# BaseShieldBrainDuino3Nov2016.net
KiCad netlist of a schematic drawn in EAGLE
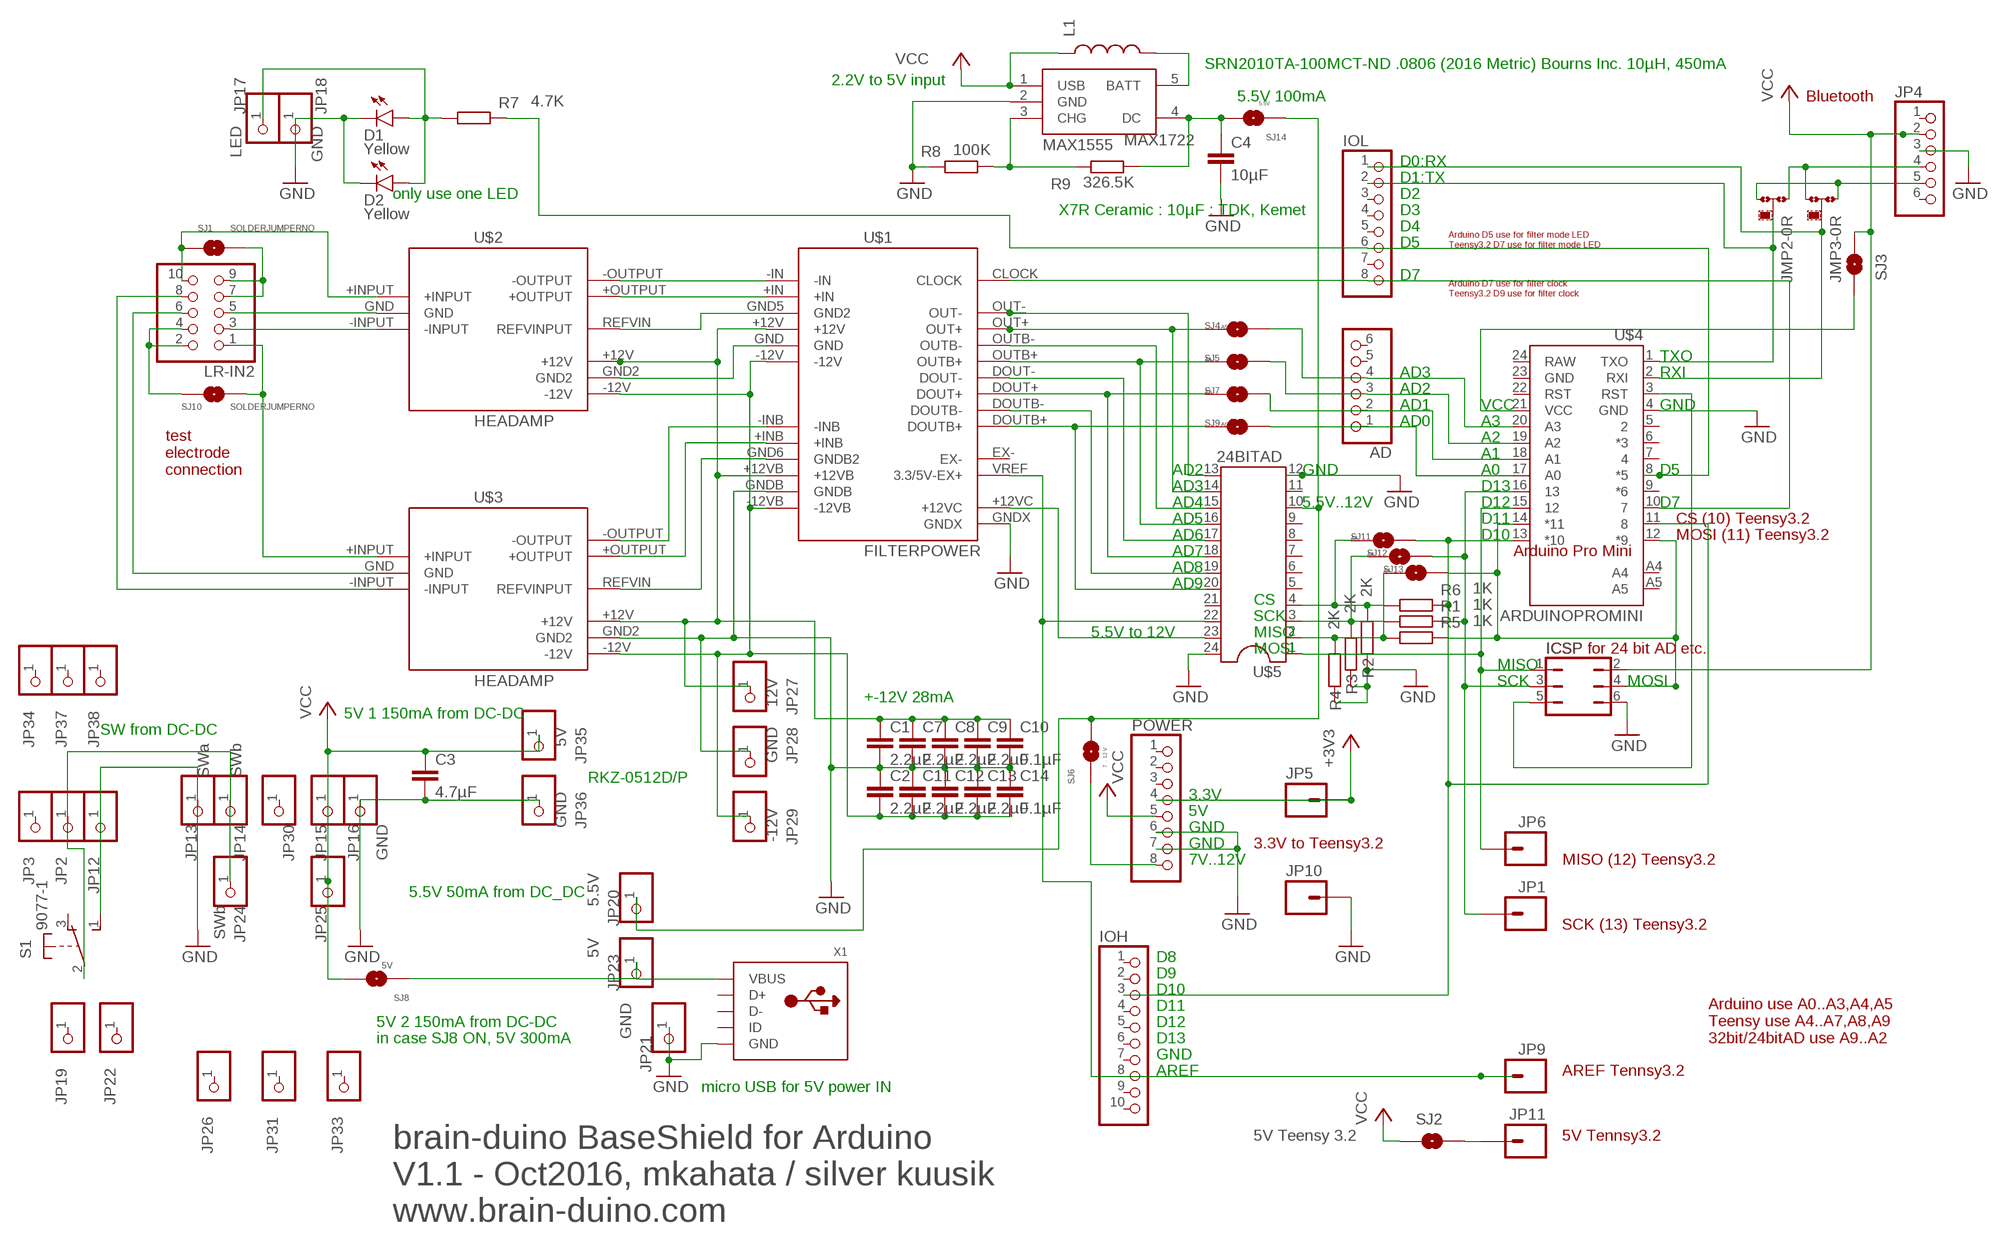
[diagram p0: schematic, sheet 1]

(export (version "E")
  (design (tool "Eeschema 10.0.6"))
  (components
    (comp (ref "AD")
      (value "PINHD-1X6")
      (footprint "eagle-import:1X06")
      (libsource (lib "eagle-import") (part "PINHD-1X6"))
    )
    (comp (ref "C1")
      (value "2.2µF")
      (footprint "eagle-import:C0402")
      (libsource (lib "eagle-import") (part "C-EUC0402"))
    )
    (comp (ref "C2")
      (value "2.2µF")
      (footprint "eagle-import:C0402")
      (libsource (lib "eagle-import") (part "C-EUC0402"))
    )
    (comp (ref "C3")
      (value "4.7µF")
      (footprint "eagle-import:C0402")
      (libsource (lib "eagle-import") (part "C-EUC0402"))
    )
    (comp (ref "C4")
      (value "10µF")
      (footprint "eagle-import:C0402")
      (libsource (lib "eagle-import") (part "C-EUC0402"))
    )
    (comp (ref "C7")
      (value "2.2µF")
      (footprint "eagle-import:C0402")
      (libsource (lib "eagle-import") (part "C-EUC0402"))
    )
    (comp (ref "C8")
      (value "2.2µF")
      (footprint "eagle-import:C0402")
      (libsource (lib "eagle-import") (part "C-EUC0402"))
    )
    (comp (ref "C9")
      (value "2.2µF")
      (footprint "eagle-import:C0402")
      (libsource (lib "eagle-import") (part "C-EUC0402"))
    )
    (comp (ref "C10")
      (value "0.1µF")
      (footprint "eagle-import:C0402")
      (libsource (lib "eagle-import") (part "C-EUC0402"))
    )
    (comp (ref "C11")
      (value "2.2µF")
      (footprint "eagle-import:C0402")
      (libsource (lib "eagle-import") (part "C-EUC0402"))
    )
    (comp (ref "C12")
      (value "2.2µF")
      (footprint "eagle-import:C0402")
      (libsource (lib "eagle-import") (part "C-EUC0402"))
    )
    (comp (ref "C13")
      (value "2.2µF")
      (footprint "eagle-import:C0402")
      (libsource (lib "eagle-import") (part "C-EUC0402"))
    )
    (comp (ref "C14")
      (value "0.1µF")
      (footprint "eagle-import:C0402")
      (libsource (lib "eagle-import") (part "C-EUC0402"))
    )
    (comp (ref "D1")
      (value "Yellow")
      (footprint "eagle-import:LED-0603")
      (libsource (lib "eagle-import") (part "LED-YELLOW0603"))
    )
    (comp (ref "D2")
      (value "Yellow")
      (footprint "eagle-import:LED-0603")
      (libsource (lib "eagle-import") (part "LED-YELLOW0603"))
    )
    (comp (ref "ICSP")
      (value "JP3Q")
      (footprint "eagle-import:JP3Q")
      (libsource (lib "eagle-import") (part "JP3Q"))
    )
    (comp (ref "IOH")
      (value "PINHD-1X10")
      (footprint "eagle-import:1X10")
      (libsource (lib "eagle-import") (part "PINHD-1X10"))
    )
    (comp (ref "IOL")
      (value "PINHD-1X8")
      (footprint "eagle-import:1X08")
      (libsource (lib "eagle-import") (part "PINHD-1X8"))
    )
    (comp (ref "JMP2")
      (value "RX")
      (footprint "eagle-import:A0R-JMP")
      (libsource (lib "eagle-import") (part "0R-JUMPA"))
    )
    (comp (ref "JMP3")
      (value "TX")
      (footprint "eagle-import:A0R-JMP")
      (libsource (lib "eagle-import") (part "0R-JUMPA"))
    )
    (comp (ref "JP1")
      (value "M01PTH")
      (footprint "eagle-import:1X01")
      (libsource (lib "eagle-import") (part "M01PTH"))
    )
    (comp (ref "JP2")
      (value "PINHD-1X1")
      (footprint "eagle-import:1X01")
      (libsource (lib "eagle-import") (part "PINHD-1X1"))
    )
    (comp (ref "JP3")
      (value "PINHD-1X1")
      (footprint "eagle-import:1X01")
      (libsource (lib "eagle-import") (part "PINHD-1X1"))
    )
    (comp (ref "JP4")
      (value "PINHD-1X6")
      (footprint "eagle-import:1X06")
      (libsource (lib "eagle-import") (part "PINHD-1X6"))
    )
    (comp (ref "JP5")
      (value "M01PTH")
      (footprint "eagle-import:1X01")
      (libsource (lib "eagle-import") (part "M01PTH"))
    )
    (comp (ref "JP6")
      (value "M01PTH")
      (footprint "eagle-import:1X01")
      (libsource (lib "eagle-import") (part "M01PTH"))
    )
    (comp (ref "JP9")
      (value "M01PTH")
      (footprint "eagle-import:1X01")
      (libsource (lib "eagle-import") (part "M01PTH"))
    )
    (comp (ref "JP10")
      (value "M01PTH")
      (footprint "eagle-import:1X01")
      (libsource (lib "eagle-import") (part "M01PTH"))
    )
    (comp (ref "JP11")
      (value "M01PTH")
      (footprint "eagle-import:1X01")
      (libsource (lib "eagle-import") (part "M01PTH"))
    )
    (comp (ref "JP12")
      (value "PINHD-1X1")
      (footprint "eagle-import:1X01")
      (libsource (lib "eagle-import") (part "PINHD-1X1"))
    )
    (comp (ref "JP13")
      (value "SWa")
      (footprint "eagle-import:1X01")
      (libsource (lib "eagle-import") (part "PINHD-1X1"))
    )
    (comp (ref "JP14")
      (value "SWb")
      (footprint "eagle-import:1X01")
      (libsource (lib "eagle-import") (part "PINHD-1X1"))
    )
    (comp (ref "JP15")
      (value "+5V")
      (footprint "eagle-import:1X01")
      (libsource (lib "eagle-import") (part "PINHD-1X1"))
    )
    (comp (ref "JP16")
      (value "GND")
      (footprint "eagle-import:1X01")
      (libsource (lib "eagle-import") (part "PINHD-1X1"))
    )
    (comp (ref "JP17")
      (value "LED")
      (footprint "eagle-import:1X01")
      (libsource (lib "eagle-import") (part "PINHD-1X1"))
    )
    (comp (ref "JP18")
      (value "GND")
      (footprint "eagle-import:1X01")
      (libsource (lib "eagle-import") (part "PINHD-1X1"))
    )
    (comp (ref "JP19")
      (value "PINHD-1X1")
      (footprint "eagle-import:1X01")
      (libsource (lib "eagle-import") (part "PINHD-1X1"))
    )
    (comp (ref "JP20")
      (value "5.5V")
      (footprint "eagle-import:1X01")
      (libsource (lib "eagle-import") (part "PINHD-1X1"))
    )
    (comp (ref "JP21")
      (value "GND")
      (footprint "eagle-import:1X01")
      (libsource (lib "eagle-import") (part "PINHD-1X1"))
    )
    (comp (ref "JP22")
      (value "PINHD-1X1")
      (footprint "eagle-import:1X01")
      (libsource (lib "eagle-import") (part "PINHD-1X1"))
    )
    (comp (ref "JP23")
      (value "5V")
      (footprint "eagle-import:1X01")
      (libsource (lib "eagle-import") (part "PINHD-1X1"))
    )
    (comp (ref "JP24")
      (value "SWb")
      (footprint "eagle-import:1X01")
      (libsource (lib "eagle-import") (part "PINHD-1X1"))
    )
    (comp (ref "JP25")
      (value "+5V")
      (footprint "eagle-import:1X01")
      (libsource (lib "eagle-import") (part "PINHD-1X1"))
    )
    (comp (ref "JP26")
      (value "PINHD-1X1")
      (footprint "eagle-import:1X01")
      (libsource (lib "eagle-import") (part "PINHD-1X1"))
    )
    (comp (ref "JP27")
      (value "12V")
      (footprint "eagle-import:1X01")
      (libsource (lib "eagle-import") (part "PINHD-1X1"))
    )
    (comp (ref "JP28")
      (value "GND")
      (footprint "eagle-import:1X01")
      (libsource (lib "eagle-import") (part "PINHD-1X1"))
    )
    (comp (ref "JP29")
      (value "-12V")
      (footprint "eagle-import:1X01")
      (libsource (lib "eagle-import") (part "PINHD-1X1"))
    )
    (comp (ref "JP30")
      (value "PINHD-1X1")
      (footprint "eagle-import:1X01")
      (libsource (lib "eagle-import") (part "PINHD-1X1"))
    )
    (comp (ref "JP31")
      (value "PINHD-1X1")
      (footprint "eagle-import:1X01")
      (libsource (lib "eagle-import") (part "PINHD-1X1"))
    )
    (comp (ref "JP33")
      (value "PINHD-1X1")
      (footprint "eagle-import:1X01")
      (libsource (lib "eagle-import") (part "PINHD-1X1"))
    )
    (comp (ref "JP34")
      (value "PINHD-1X1")
      (footprint "eagle-import:1X01")
      (libsource (lib "eagle-import") (part "PINHD-1X1"))
    )
    (comp (ref "JP35")
      (value "5V")
      (footprint "eagle-import:1X01")
      (libsource (lib "eagle-import") (part "PINHD-1X1"))
    )
    (comp (ref "JP36")
      (value "GND")
      (footprint "eagle-import:1X01")
      (libsource (lib "eagle-import") (part "PINHD-1X1"))
    )
    (comp (ref "JP37")
      (value "PINHD-1X1")
      (footprint "eagle-import:1X01")
      (libsource (lib "eagle-import") (part "PINHD-1X1"))
    )
    (comp (ref "JP38")
      (value "PINHD-1X1")
      (footprint "eagle-import:1X01")
      (libsource (lib "eagle-import") (part "PINHD-1X1"))
    )
    (comp (ref "L1")
      (value "INDUCTOR0805")
      (footprint "eagle-import:0805")
      (libsource (lib "eagle-import") (part "INDUCTOR0805"))
    )
    (comp (ref "LR-IN2")
      (value "PINHD-2X5/90")
      (footprint "eagle-import:2X05_90")
      (libsource (lib "eagle-import") (part "PINHD-2X5/90"))
    )
    (comp (ref "MAX1722")
      (value "MAX1555")
      (footprint "eagle-import:SOT23-5")
      (libsource (lib "eagle-import") (part "MAX1555"))
    )
    (comp (ref "POWER")
      (value "PINHD-1X8")
      (footprint "eagle-import:1X08")
      (libsource (lib "eagle-import") (part "PINHD-1X8"))
    )
    (comp (ref "R1")
      (value "1K")
      (footprint "eagle-import:R0402")
      (libsource (lib "eagle-import") (part "R-EU_R0402"))
    )
    (comp (ref "R2")
      (value "2K")
      (footprint "eagle-import:R0402")
      (libsource (lib "eagle-import") (part "R-EU_R0402"))
    )
    (comp (ref "R3")
      (value "2K")
      (footprint "eagle-import:R0402")
      (libsource (lib "eagle-import") (part "R-EU_R0402"))
    )
    (comp (ref "R4")
      (value "2K")
      (footprint "eagle-import:R0402")
      (libsource (lib "eagle-import") (part "R-EU_R0402"))
    )
    (comp (ref "R5")
      (value "1K")
      (footprint "eagle-import:R0402")
      (libsource (lib "eagle-import") (part "R-EU_R0402"))
    )
    (comp (ref "R6")
      (value "1K")
      (footprint "eagle-import:R0402")
      (libsource (lib "eagle-import") (part "R-EU_R0402"))
    )
    (comp (ref "R7")
      (value "4.7K")
      (footprint "eagle-import:R0402")
      (libsource (lib "eagle-import") (part "R-EU_R0402"))
    )
    (comp (ref "R8")
      (value "100K")
      (footprint "eagle-import:R0402")
      (libsource (lib "eagle-import") (part "R-EU_R0402"))
    )
    (comp (ref "R9")
      (value "326.5K")
      (footprint "eagle-import:R0402")
      (libsource (lib "eagle-import") (part "R-EU_R0402"))
    )
    (comp (ref "S1")
      (value "9077-1")
      (footprint "eagle-import:9077-1")
      (libsource (lib "eagle-import") (part "9077-1"))
    )
    (comp (ref "SJ1")
      (value "SOLDERJUMPERNO")
      (footprint "eagle-import:SJ_2S-NO")
      (libsource (lib "eagle-import") (part "SOLDERJUMPERNO"))
    )
    (comp (ref "SJ2")
      (value "5V Teensy 3.2")
      (footprint "eagle-import:SJ_2S-NO")
      (libsource (lib "eagle-import") (part "SOLDERJUMPERNO"))
    )
    (comp (ref "SJ3")
      (value "5V Arduino Pro Mini")
      (footprint "eagle-import:SJ_2S-NO")
      (libsource (lib "eagle-import") (part "SOLDERJUMPERNO"))
    )
    (comp (ref "SJ4")
      (value "A5")
      (footprint "eagle-import:SJ_2S-NO")
      (libsource (lib "eagle-import") (part "SOLDERJUMPERNO"))
    )
    (comp (ref "SJ5")
      (value "A4")
      (footprint "eagle-import:SJ_2S-NO")
      (libsource (lib "eagle-import") (part "SOLDERJUMPERNO"))
    )
    (comp (ref "SJ6")
      (value "7 .. 12 V")
      (footprint "eagle-import:SJ_2S-NO")
      (libsource (lib "eagle-import") (part "SOLDERJUMPERNO"))
    )
    (comp (ref "SJ7")
      (value "A2")
      (footprint "eagle-import:SJ_2S-NO")
      (libsource (lib "eagle-import") (part "SOLDERJUMPERNO"))
    )
    (comp (ref "SJ8")
      (value "5V")
      (footprint "eagle-import:SJ_2S-NO")
      (libsource (lib "eagle-import") (part "SOLDERJUMPERNO"))
    )
    (comp (ref "SJ9")
      (value "A0")
      (footprint "eagle-import:SJ_2S-NO")
      (libsource (lib "eagle-import") (part "SOLDERJUMPERNO"))
    )
    (comp (ref "SJ10")
      (value "SOLDERJUMPERNO")
      (footprint "eagle-import:SJ_2S-NO")
      (libsource (lib "eagle-import") (part "SOLDERJUMPERNO"))
    )
    (comp (ref "SJ11")
      (value "A4")
      (footprint "eagle-import:SJ_2S-NO")
      (libsource (lib "eagle-import") (part "SOLDERJUMPERNO"))
    )
    (comp (ref "SJ12")
      (value "A4")
      (footprint "eagle-import:SJ_2S-NO")
      (libsource (lib "eagle-import") (part "SOLDERJUMPERNO"))
    )
    (comp (ref "SJ13")
      (value "A4")
      (footprint "eagle-import:SJ_2S-NO")
      (libsource (lib "eagle-import") (part "SOLDERJUMPERNO"))
    )
    (comp (ref "SJ14")
      (value "5.5V")
      (footprint "eagle-import:SJ_2S-NO")
      (libsource (lib "eagle-import") (part "SOLDERJUMPERNO"))
    )
    (comp (ref "U$1")
      (value "FILTERPOWER")
      (footprint "eagle-import:FILTERPOWER")
      (libsource (lib "eagle-import") (part "FILTERPOWER"))
    )
    (comp (ref "U$2")
      (value "HEADAMP")
      (footprint "eagle-import:HEADAMP")
      (libsource (lib "eagle-import") (part "HEADAMP"))
    )
    (comp (ref "U$3")
      (value "HEADAMP")
      (footprint "eagle-import:HEADAMP")
      (libsource (lib "eagle-import") (part "HEADAMP"))
    )
    (comp (ref "U$4")
      (value "ARDUINOPROMINI")
      (footprint "eagle-import:ARDUINOPROMINI")
      (libsource (lib "eagle-import") (part "ARDUINOPROMINI"))
    )
    (comp (ref "U$5")
      (value "24BITAD")
      (footprint "eagle-import:24BITAD")
      (libsource (lib "eagle-import") (part "24BITAD"))
    )
    (comp (ref "X1")
      (value "USB_MICRO_20329_V2")
      (footprint "eagle-import:4UCONN_20329_V2")
      (libsource (lib "eagle-import") (part "USB_MICRO_20329_V2"))
    )
  )
  (nets
    (net (code "1") (name "+3V3") (class "Default")
      (node (ref "JP5") (pin "1") (pinfunction "1_1") (pintype "passive"))
      (node (ref "POWER") (pin "4") (pinfunction "4_4") (pintype "passive"))
    )
    (net (code "2") (name "GND") (class "Default")
      (node (ref "C1") (pin "2") (pinfunction "2_2") (pintype "passive"))
      (node (ref "C10") (pin "2") (pinfunction "2_2") (pintype "passive"))
      (node (ref "C11") (pin "1") (pinfunction "1_1") (pintype "passive"))
      (node (ref "C12") (pin "1") (pinfunction "1_1") (pintype "passive"))
      (node (ref "C13") (pin "1") (pinfunction "1_1") (pintype "passive"))
      (node (ref "C14") (pin "1") (pinfunction "1_1") (pintype "passive"))
      (node (ref "C2") (pin "1") (pinfunction "1_1") (pintype "passive"))
      (node (ref "C3") (pin "2") (pinfunction "2_2") (pintype "passive"))
      (node (ref "C4") (pin "2") (pinfunction "2_2") (pintype "passive"))
      (node (ref "C7") (pin "2") (pinfunction "2_2") (pintype "passive"))
      (node (ref "C8") (pin "2") (pinfunction "2_2") (pintype "passive"))
      (node (ref "C9") (pin "2") (pinfunction "2_2") (pintype "passive"))
      (node (ref "D1") (pin "C") (pinfunction "C_C") (pintype "passive"))
      (node (ref "D2") (pin "C") (pinfunction "C_C") (pintype "passive"))
      (node (ref "ICSP") (pin "6") (pinfunction "6_6") (pintype "passive"))
      (node (ref "JP10") (pin "1") (pinfunction "1_1") (pintype "passive"))
      (node (ref "JP12") (pin "1") (pinfunction "1_1") (pintype "passive"))
      (node (ref "JP13") (pin "1") (pinfunction "1_1") (pintype "passive"))
      (node (ref "JP16") (pin "1") (pinfunction "1_1") (pintype "passive"))
      (node (ref "JP18") (pin "1") (pinfunction "1_1") (pintype "passive"))
      (node (ref "JP21") (pin "1") (pinfunction "1_1") (pintype "passive"))
      (node (ref "JP28") (pin "1") (pinfunction "1_1") (pintype "passive"))
      (node (ref "JP36") (pin "1") (pinfunction "1_1") (pintype "passive"))
      (node (ref "JP4") (pin "3") (pinfunction "3_3") (pintype "passive"))
      (node (ref "MAX1722") (pin "2") (pinfunction "GND_2") (pintype "bidirectional"))
      (node (ref "POWER") (pin "6") (pinfunction "6_6") (pintype "passive"))
      (node (ref "POWER") (pin "7") (pinfunction "7_7") (pintype "passive"))
      (node (ref "R2") (pin "1") (pinfunction "1_1") (pintype "passive"))
      (node (ref "R3") (pin "1") (pinfunction "1_1") (pintype "passive"))
      (node (ref "R4") (pin "1") (pinfunction "1_1") (pintype "passive"))
      (node (ref "R8") (pin "1") (pinfunction "1_1") (pintype "passive"))
      (node (ref "S1") (pin "1") (pinfunction "S_1") (pintype "passive"))
      (node (ref "U$1") (pin "GNDB") (pinfunction "GNDB_GNDB") (pintype "power_in"))
      (node (ref "U$1") (pin "GNDX") (pinfunction "GNDX_GNDX") (pintype "power_in"))
      (node (ref "U$3") (pin "GND2") (pinfunction "GND2_GND2") (pintype "bidirectional"))
      (node (ref "U$4") (pin "4") (pinfunction "GND_4") (pintype "bidirectional"))
      (node (ref "U$5") (pin "12") (pinfunction "12_12") (pintype "passive"))
      (node (ref "U$5") (pin "24") (pinfunction "24_24") (pintype "passive"))
      (node (ref "X1") (pin "BASE@1") (pinfunction "GND_BASE@1") (pintype "power_in"))
      (node (ref "X1") (pin "BASE@2") (pinfunction "GND_BASE@2") (pintype "power_in"))
      (node (ref "X1") (pin "GND") (pinfunction "GND_GND") (pintype "power_in"))
      (node (ref "X1") (pin "SPRT@1") (pinfunction "GND_SPRT@1") (pintype "power_in"))
      (node (ref "X1") (pin "SPRT@2") (pinfunction "GND_SPRT@2") (pintype "power_in"))
      (node (ref "X1") (pin "SPRT@3") (pinfunction "GND_SPRT@3") (pintype "power_in"))
      (node (ref "X1") (pin "SPRT@4") (pinfunction "GND_SPRT@4") (pintype "power_in"))
    )
    (net (code "3") (name "Net-(C1-Pad1)") (class "Default")
      (node (ref "C1") (pin "1") (pinfunction "1_1") (pintype "passive"))
      (node (ref "C10") (pin "1") (pinfunction "1_1") (pintype "passive"))
      (node (ref "C7") (pin "1") (pinfunction "1_1") (pintype "passive"))
      (node (ref "C8") (pin "1") (pinfunction "1_1") (pintype "passive"))
      (node (ref "C9") (pin "1") (pinfunction "1_1") (pintype "passive"))
      (node (ref "JP27") (pin "1") (pinfunction "1_1") (pintype "passive"))
      (node (ref "U$1") (pin "+12V") (pinfunction "+12V_+12V") (pintype "bidirectional"))
      (node (ref "U$1") (pin "+12VB") (pinfunction "+12VB_+12VB") (pintype "bidirectional"))
      (node (ref "U$2") (pin "+12V") (pinfunction "+12V_+12V") (pintype "bidirectional"))
      (node (ref "U$3") (pin "+12V") (pinfunction "+12V_+12V") (pintype "bidirectional"))
    )
    (net (code "4") (name "Net-(C11-Pad2)") (class "Default")
      (node (ref "C11") (pin "2") (pinfunction "2_2") (pintype "passive"))
      (node (ref "C12") (pin "2") (pinfunction "2_2") (pintype "passive"))
      (node (ref "C13") (pin "2") (pinfunction "2_2") (pintype "passive"))
      (node (ref "C14") (pin "2") (pinfunction "2_2") (pintype "passive"))
      (node (ref "C2") (pin "2") (pinfunction "2_2") (pintype "passive"))
      (node (ref "JP29") (pin "1") (pinfunction "1_1") (pintype "passive"))
      (node (ref "U$1") (pin "-12V") (pinfunction "-12V_-12V") (pintype "bidirectional"))
      (node (ref "U$1") (pin "-12VB") (pinfunction "-12VB_-12VB") (pintype "bidirectional"))
      (node (ref "U$2") (pin "-12V") (pinfunction "-12V_-12V") (pintype "bidirectional"))
      (node (ref "U$3") (pin "-12V") (pinfunction "-12V_-12V") (pintype "bidirectional"))
    )
    (net (code "5") (name "Net-(D1-PadA)") (class "Default")
      (node (ref "D1") (pin "A") (pinfunction "A_A") (pintype "passive"))
      (node (ref "D2") (pin "A") (pinfunction "A_A") (pintype "passive"))
      (node (ref "JP17") (pin "1") (pinfunction "1_1") (pintype "passive"))
      (node (ref "R7") (pin "1") (pinfunction "1_1") (pintype "passive"))
    )
    (net (code "6") (name "Net-(ICSP-Pad5)") (class "Default")
      (node (ref "ICSP") (pin "5") (pinfunction "5_5") (pintype "passive"))
      (node (ref "U$4") (pin "3") (pinfunction "RST_3") (pintype "bidirectional"))
    )
    (net (code "7") (name "Net-(JMP2-Pad1)") (class "Default")
      (node (ref "JMP2") (pin "1") (pinfunction "1_1") (pintype "passive"))
      (node (ref "JMP3") (pin "3") (pinfunction "3_3") (pintype "passive"))
      (node (ref "JP4") (pin "4") (pinfunction "4_4") (pintype "passive"))
    )
    (net (code "8") (name "Net-(JMP2-Pad3)") (class "Default")
      (node (ref "JMP2") (pin "3") (pinfunction "3_3") (pintype "passive"))
      (node (ref "JMP3") (pin "1") (pinfunction "1_1") (pintype "passive"))
      (node (ref "JP4") (pin "5") (pinfunction "5_5") (pintype "passive"))
    )
    (net (code "9") (name "Net-(JP11-Pad1)") (class "Default")
      (node (ref "JP11") (pin "1") (pinfunction "1_1") (pintype "passive"))
      (node (ref "SJ2") (pin "2") (pinfunction "2_2") (pintype "passive"))
    )
    (net (code "10") (name "Net-(JP20-Pad1)") (class "Default")
      (node (ref "JP20") (pin "1") (pinfunction "1_1") (pintype "passive"))
      (node (ref "SJ14") (pin "1") (pinfunction "1_1") (pintype "passive"))
      (node (ref "SJ6") (pin "2") (pinfunction "2_2") (pintype "passive"))
      (node (ref "U$5") (pin "10") (pinfunction "10_10") (pintype "passive"))
    )
    (net (code "11") (name "Net-(JP23-Pad1)") (class "Default")
      (node (ref "JP23") (pin "1") (pinfunction "1_1") (pintype "passive"))
      (node (ref "SJ8") (pin "1") (pinfunction "1_1") (pintype "passive"))
      (node (ref "X1") (pin "VBUS") (pinfunction "VBUS_VBUS") (pintype "power_in"))
    )
    (net (code "12") (name "Net-(LR-IN2-Pad1)") (class "Default")
      (node (ref "LR-IN2") (pin "1") (pinfunction "1_1") (pintype "passive"))
      (node (ref "SJ10") (pin "2") (pinfunction "2_2") (pintype "passive"))
      (node (ref "U$3") (pin "+INPUT") (pinfunction "+INPUT_+INPUT") (pintype "bidirectional"))
    )
    (net (code "13") (name "Net-(LR-IN2-Pad2)") (class "Default")
      (node (ref "LR-IN2") (pin "2") (pinfunction "2_2") (pintype "passive"))
      (node (ref "LR-IN2") (pin "4") (pinfunction "4_4") (pintype "passive"))
      (node (ref "SJ10") (pin "1") (pinfunction "1_1") (pintype "passive"))
    )
    (net (code "14") (name "Net-(LR-IN2-Pad3)") (class "Default")
      (node (ref "LR-IN2") (pin "3") (pinfunction "3_3") (pintype "passive"))
      (node (ref "U$2") (pin "-INPUT") (pinfunction "-INPUT_-INPUT") (pintype "bidirectional"))
    )
    (net (code "15") (name "Net-(LR-IN2-Pad5)") (class "Default")
      (node (ref "LR-IN2") (pin "5") (pinfunction "5_5") (pintype "passive"))
      (node (ref "U$2") (pin "GND") (pinfunction "GND_GND") (pintype "bidirectional"))
    )
    (net (code "16") (name "Net-(LR-IN2-Pad6)") (class "Default")
      (node (ref "LR-IN2") (pin "6") (pinfunction "6_6") (pintype "passive"))
      (node (ref "U$3") (pin "GND") (pinfunction "GND_GND") (pintype "bidirectional"))
    )
    (net (code "17") (name "Net-(LR-IN2-Pad7)") (class "Default")
      (node (ref "LR-IN2") (pin "7") (pinfunction "7_7") (pintype "passive"))
      (node (ref "LR-IN2") (pin "9") (pinfunction "9_9") (pintype "passive"))
      (node (ref "SJ1") (pin "2") (pinfunction "2_2") (pintype "passive"))
    )
    (net (code "18") (name "Net-(LR-IN2-Pad8)") (class "Default")
      (node (ref "LR-IN2") (pin "8") (pinfunction "8_8") (pintype "passive"))
      (node (ref "U$3") (pin "-INPUT") (pinfunction "-INPUT_-INPUT") (pintype "bidirectional"))
    )
    (net (code "19") (name "Net-(LR-IN2-Pad10)") (class "Default")
      (node (ref "LR-IN2") (pin "10") (pinfunction "10_10") (pintype "passive"))
      (node (ref "SJ1") (pin "1") (pinfunction "1_1") (pintype "passive"))
      (node (ref "U$2") (pin "+INPUT") (pinfunction "+INPUT_+INPUT") (pintype "bidirectional"))
    )
    (net (code "20") (name "Net-(MAX1722-BATT)") (class "Default")
      (node (ref "L1") (pin "2") (pinfunction "2_2") (pintype "passive"))
      (node (ref "MAX1722") (pin "5") (pinfunction "BATT_5") (pintype "bidirectional"))
    )
    (net (code "21") (name "Net-(MAX1722-CHG)") (class "Default")
      (node (ref "MAX1722") (pin "3") (pinfunction "CHG_3") (pintype "bidirectional"))
      (node (ref "R8") (pin "2") (pinfunction "2_2") (pintype "passive"))
      (node (ref "R9") (pin "1") (pinfunction "1_1") (pintype "passive"))
    )
    (net (code "22") (name "Net-(MAX1722-DC)") (class "Default")
      (node (ref "C4") (pin "1") (pinfunction "1_1") (pintype "passive"))
      (node (ref "MAX1722") (pin "4") (pinfunction "DC_4") (pintype "bidirectional"))
      (node (ref "R9") (pin "2") (pinfunction "2_2") (pintype "passive"))
      (node (ref "SJ14") (pin "2") (pinfunction "2_2") (pintype "passive"))
    )
    (net (code "23") (name "Net-(POWER-Pad8)") (class "Default")
      (node (ref "POWER") (pin "8") (pinfunction "8_8") (pintype "passive"))
      (node (ref "SJ6") (pin "1") (pinfunction "1_1") (pintype "passive"))
    )
    (net (code "24") (name "Net-(R1-Pad1)") (class "Default")
      (node (ref "R1") (pin "1") (pinfunction "1_1") (pintype "passive"))
      (node (ref "R3") (pin "2") (pinfunction "2_2") (pintype "passive"))
      (node (ref "SJ12") (pin "1") (pinfunction "1_1") (pintype "passive"))
      (node (ref "U$5") (pin "3") (pinfunction "3_3") (pintype "passive"))
    )
    (net (code "25") (name "Net-(R2-Pad2)") (class "Default")
      (node (ref "R2") (pin "2") (pinfunction "2_2") (pintype "passive"))
      (node (ref "R6") (pin "1") (pinfunction "1_1") (pintype "passive"))
      (node (ref "SJ11") (pin "1") (pinfunction "1_1") (pintype "passive"))
      (node (ref "U$5") (pin "4") (pinfunction "4_4") (pintype "passive"))
    )
    (net (code "26") (name "Net-(R4-Pad2)") (class "Default")
      (node (ref "R4") (pin "2") (pinfunction "2_2") (pintype "passive"))
      (node (ref "R5") (pin "1") (pinfunction "1_1") (pintype "passive"))
      (node (ref "SJ13") (pin "1") (pinfunction "1_1") (pintype "passive"))
      (node (ref "U$5") (pin "2") (pinfunction "2_2") (pintype "passive"))
    )
    (net (code "27") (name "Net-(S1-P)") (class "Default")
      (node (ref "JP14") (pin "1") (pinfunction "1_1") (pintype "passive"))
      (node (ref "JP2") (pin "1") (pinfunction "1_1") (pintype "passive"))
      (node (ref "JP24") (pin "1") (pinfunction "1_1") (pintype "passive"))
      (node (ref "S1") (pin "2") (pinfunction "P_2") (pintype "passive"))
    )
    (net (code "28") (name "Net-(SJ4-Pad1)") (class "Default")
      (node (ref "SJ4") (pin "1") (pinfunction "1_1") (pintype "passive"))
      (node (ref "U$1") (pin "OUT+") (pinfunction "OUT+_OUT+") (pintype "power_in"))
      (node (ref "U$5") (pin "14") (pinfunction "14_14") (pintype "passive"))
    )
    (net (code "29") (name "Net-(SJ5-Pad1)") (class "Default")
      (node (ref "SJ5") (pin "1") (pinfunction "1_1") (pintype "passive"))
      (node (ref "U$1") (pin "OUTB+") (pinfunction "OUTB+_OUTB+") (pintype "power_in"))
      (node (ref "U$5") (pin "16") (pinfunction "16_16") (pintype "passive"))
    )
    (net (code "30") (name "Net-(SJ7-Pad1)") (class "Default")
      (node (ref "SJ7") (pin "1") (pinfunction "1_1") (pintype "passive"))
      (node (ref "U$1") (pin "DOUT+") (pinfunction "DOUT+_DOUT+") (pintype "output"))
      (node (ref "U$5") (pin "18") (pinfunction "18_18") (pintype "passive"))
    )
    (net (code "31") (name "Net-(SJ9-Pad1)") (class "Default")
      (node (ref "SJ9") (pin "1") (pinfunction "1_1") (pintype "passive"))
      (node (ref "U$1") (pin "DOUTB+") (pinfunction "DOUTB+_DOUTB+") (pintype "output"))
      (node (ref "U$5") (pin "20") (pinfunction "20_20") (pintype "passive"))
    )
    (net (code "32") (name "Net-(U$1-3.3{slash}5V-EX+)") (class "Default")
      (node (ref "IOH") (pin "8") (pinfunction "8_8") (pintype "passive"))
      (node (ref "JP9") (pin "1") (pinfunction "1_1") (pintype "passive"))
      (node (ref "U$1") (pin "VREF") (pinfunction "3.3/5V-EX+_VREF") (pintype "output"))
      (node (ref "U$5") (pin "22") (pinfunction "22_22") (pintype "passive"))
    )
    (net (code "33") (name "Net-(U$1-GND2)") (class "Default")
      (node (ref "U$1") (pin "GND5") (pinfunction "GND2_GND5") (pintype "power_in"))
      (node (ref "U$2") (pin "REFVIN") (pinfunction "REFVINPUT_REFVIN") (pintype "bidirectional"))
    )
    (net (code "34") (name "Net-(U$1-GNDB2)") (class "Default")
      (node (ref "U$1") (pin "GND6") (pinfunction "GNDB2_GND6") (pintype "power_in"))
      (node (ref "U$3") (pin "REFVIN") (pinfunction "REFVINPUT_REFVIN") (pintype "bidirectional"))
    )
    (net (code "35") (name "Net-(U$1-Pad+12VC)") (class "Default")
      (node (ref "U$1") (pin "+12VC") (pinfunction "+12VC_+12VC") (pintype "power_in"))
      (node (ref "U$5") (pin "23") (pinfunction "23_23") (pintype "passive"))
    )
    (net (code "36") (name "Net-(U$1-Pad+IN)") (class "Default")
      (node (ref "U$1") (pin "+IN") (pinfunction "+IN_+IN") (pintype "input"))
      (node (ref "U$2") (pin "+OUTPUT") (pinfunction "+OUTPUT_+OUTPUT") (pintype "bidirectional"))
    )
    (net (code "37") (name "Net-(U$1-Pad+INB)") (class "Default")
      (node (ref "U$1") (pin "+INB") (pinfunction "+INB_+INB") (pintype "bidirectional"))
      (node (ref "U$3") (pin "+OUTPUT") (pinfunction "+OUTPUT_+OUTPUT") (pintype "bidirectional"))
    )
    (net (code "38") (name "Net-(U$1-Pad-IN)") (class "Default")
      (node (ref "U$1") (pin "-IN") (pinfunction "-IN_-IN") (pintype "input"))
      (node (ref "U$2") (pin "-OUTPUT") (pinfunction "-OUTPUT_-OUTPUT") (pintype "bidirectional"))
    )
    (net (code "39") (name "Net-(U$1-Pad-INB)") (class "Default")
      (node (ref "U$1") (pin "-INB") (pinfunction "-INB_-INB") (pintype "bidirectional"))
      (node (ref "U$3") (pin "-OUTPUT") (pinfunction "-OUTPUT_-OUTPUT") (pintype "bidirectional"))
    )
    (net (code "40") (name "Net-(U$1-PadDOUT-)") (class "Default")
      (node (ref "U$1") (pin "DOUT-") (pinfunction "DOUT-_DOUT-") (pintype "output"))
      (node (ref "U$5") (pin "17") (pinfunction "17_17") (pintype "passive"))
    )
    (net (code "41") (name "Net-(U$1-PadDOUTB-)") (class "Default")
      (node (ref "U$1") (pin "DOUTB-") (pinfunction "DOUTB-_DOUTB-") (pintype "output"))
      (node (ref "U$5") (pin "19") (pinfunction "19_19") (pintype "passive"))
    )
    (net (code "42") (name "Net-(U$1-PadGND)") (class "Default")
      (node (ref "U$1") (pin "GND") (pinfunction "GND_GND") (pintype "power_in"))
      (node (ref "U$2") (pin "GND2") (pinfunction "GND2_GND2") (pintype "bidirectional"))
    )
    (net (code "43") (name "Net-(U$1-PadOUT-)") (class "Default")
      (node (ref "U$1") (pin "OUT-") (pinfunction "OUT-_OUT-") (pintype "bidirectional"))
      (node (ref "U$5") (pin "13") (pinfunction "13_13") (pintype "passive"))
    )
    (net (code "44") (name "Net-(U$1-PadOUTB-)") (class "Default")
      (node (ref "U$1") (pin "OUTB-") (pinfunction "OUTB-_OUTB-") (pintype "output"))
      (node (ref "U$5") (pin "15") (pinfunction "15_15") (pintype "passive"))
    )
    (net (code "45") (name "Net-(U$4-*5)") (class "Default")
      (node (ref "IOL") (pin "6") (pinfunction "6_6") (pintype "passive"))
      (node (ref "R7") (pin "2") (pinfunction "2_2") (pintype "passive"))
      (node (ref "U$4") (pin "8") (pinfunction "*5_8") (pintype "bidirectional"))
    )
    (net (code "46") (name "Net-(U$4-*10)") (class "Default")
      (node (ref "IOH") (pin "3") (pinfunction "3_3") (pintype "passive"))
      (node (ref "R6") (pin "2") (pinfunction "2_2") (pintype "passive"))
      (node (ref "SJ11") (pin "2") (pinfunction "2_2") (pintype "passive"))
      (node (ref "U$4") (pin "11") (pinfunction "8_11") (pintype "bidirectional"))
      (node (ref "U$4") (pin "13") (pinfunction "*10_13") (pintype "bidirectional"))
    )
    (net (code "47") (name "Net-(U$4-*11)") (class "Default")
      (node (ref "ICSP") (pin "4") (pinfunction "4_4") (pintype "passive"))
      (node (ref "R5") (pin "2") (pinfunction "2_2") (pintype "passive"))
      (node (ref "SJ13") (pin "2") (pinfunction "2_2") (pintype "passive"))
      (node (ref "U$4") (pin "12") (pinfunction "*9_12") (pintype "bidirectional"))
      (node (ref "U$4") (pin "14") (pinfunction "*11_14") (pintype "bidirectional"))
    )
    (net (code "48") (name "Net-(U$4-7)") (class "Default")
      (node (ref "IOL") (pin "8") (pinfunction "8_8") (pintype "passive"))
      (node (ref "U$1") (pin "CLOCK") (pinfunction "CLOCK_CLOCK") (pintype "input"))
      (node (ref "U$4") (pin "10") (pinfunction "7_10") (pintype "bidirectional"))
    )
    (net (code "49") (name "Net-(U$4-12)") (class "Default")
      (node (ref "ICSP") (pin "1") (pinfunction "1_1") (pintype "passive"))
      (node (ref "JP6") (pin "1") (pinfunction "1_1") (pintype "passive"))
      (node (ref "U$4") (pin "15") (pinfunction "12_15") (pintype "bidirectional"))
      (node (ref "U$5") (pin "1") (pinfunction "1_1") (pintype "passive"))
    )
    (net (code "50") (name "Net-(U$4-13)") (class "Default")
      (node (ref "ICSP") (pin "3") (pinfunction "3_3") (pintype "passive"))
      (node (ref "JP1") (pin "1") (pinfunction "1_1") (pintype "passive"))
      (node (ref "R1") (pin "2") (pinfunction "2_2") (pintype "passive"))
      (node (ref "SJ12") (pin "2") (pinfunction "2_2") (pintype "passive"))
      (node (ref "U$4") (pin "16") (pinfunction "13_16") (pintype "bidirectional"))
    )
    (net (code "51") (name "Net-(U$4-A0)") (class "Default")
      (node (ref "AD") (pin "1") (pinfunction "1_1") (pintype "passive"))
      (node (ref "SJ9") (pin "2") (pinfunction "2_2") (pintype "passive"))
      (node (ref "U$4") (pin "17") (pinfunction "A0_17") (pintype "bidirectional"))
    )
    (net (code "52") (name "Net-(U$4-A1)") (class "Default")
      (node (ref "AD") (pin "2") (pinfunction "2_2") (pintype "passive"))
      (node (ref "SJ7") (pin "2") (pinfunction "2_2") (pintype "passive"))
      (node (ref "U$4") (pin "18") (pinfunction "A1_18") (pintype "bidirectional"))
    )
    (net (code "53") (name "Net-(U$4-A2)") (class "Default")
      (node (ref "AD") (pin "3") (pinfunction "3_3") (pintype "passive"))
      (node (ref "SJ5") (pin "2") (pinfunction "2_2") (pintype "passive"))
      (node (ref "U$4") (pin "19") (pinfunction "A2_19") (pintype "bidirectional"))
    )
    (net (code "54") (name "Net-(U$4-A3)") (class "Default")
      (node (ref "AD") (pin "4") (pinfunction "4_4") (pintype "passive"))
      (node (ref "SJ4") (pin "2") (pinfunction "2_2") (pintype "passive"))
      (node (ref "U$4") (pin "20") (pinfunction "A3_20") (pintype "bidirectional"))
    )
    (net (code "55") (name "Net-(U$4-RXI)") (class "Default")
      (node (ref "IOL") (pin "1") (pinfunction "1_1") (pintype "passive"))
      (node (ref "JMP3") (pin "2") (pinfunction "2_2") (pintype "passive"))
      (node (ref "U$4") (pin "2") (pinfunction "RXI_2") (pintype "bidirectional"))
    )
    (net (code "56") (name "Net-(U$4-TXO)") (class "Default")
      (node (ref "IOL") (pin "2") (pinfunction "2_2") (pintype "passive"))
      (node (ref "JMP2") (pin "2") (pinfunction "2_2") (pintype "passive"))
      (node (ref "U$4") (pin "1") (pinfunction "TXO_1") (pintype "bidirectional"))
    )
    (net (code "57") (name "Net-(U$4-VCC)") (class "Default")
      (node (ref "SJ3") (pin "1") (pinfunction "1_1") (pintype "passive"))
      (node (ref "U$4") (pin "21") (pinfunction "VCC_21") (pintype "bidirectional"))
    )
    (net (code "58") (name "VCC") (class "Default")
      (node (ref "C3") (pin "1") (pinfunction "1_1") (pintype "passive"))
      (node (ref "ICSP") (pin "2") (pinfunction "2_2") (pintype "passive"))
      (node (ref "JP15") (pin "1") (pinfunction "1_1") (pintype "passive"))
      (node (ref "JP25") (pin "1") (pinfunction "1_1") (pintype "passive"))
      (node (ref "JP35") (pin "1") (pinfunction "1_1") (pintype "passive"))
      (node (ref "JP4") (pin "2") (pinfunction "2_2") (pintype "passive"))
      (node (ref "L1") (pin "1") (pinfunction "1_1") (pintype "passive"))
      (node (ref "MAX1722") (pin "1") (pinfunction "USB_1") (pintype "bidirectional"))
      (node (ref "POWER") (pin "5") (pinfunction "5_5") (pintype "passive"))
      (node (ref "SJ2") (pin "1") (pinfunction "1_1") (pintype "passive"))
      (node (ref "SJ3") (pin "2") (pinfunction "2_2") (pintype "passive"))
      (node (ref "SJ8") (pin "2") (pinfunction "2_2") (pintype "passive"))
    )
    (net (code "59") (name "unconnected-(AD-Pad5)") (class "Default")
      (node (ref "AD") (pin "5") (pinfunction "5_5") (pintype "passive"))
    )
    (net (code "60") (name "unconnected-(AD-Pad6)") (class "Default")
      (node (ref "AD") (pin "6") (pinfunction "6_6") (pintype "passive"))
    )
    (net (code "61") (name "unconnected-(IOH-Pad1)") (class "Default")
      (node (ref "IOH") (pin "1") (pinfunction "1_1") (pintype "passive"))
    )
    (net (code "62") (name "unconnected-(IOH-Pad2)") (class "Default")
      (node (ref "IOH") (pin "2") (pinfunction "2_2") (pintype "passive"))
    )
    (net (code "63") (name "unconnected-(IOH-Pad4)") (class "Default")
      (node (ref "IOH") (pin "4") (pinfunction "4_4") (pintype "passive"))
    )
    (net (code "64") (name "unconnected-(IOH-Pad5)") (class "Default")
      (node (ref "IOH") (pin "5") (pinfunction "5_5") (pintype "passive"))
    )
    (net (code "65") (name "unconnected-(IOH-Pad6)") (class "Default")
      (node (ref "IOH") (pin "6") (pinfunction "6_6") (pintype "passive"))
    )
    (net (code "66") (name "unconnected-(IOH-Pad7)") (class "Default")
      (node (ref "IOH") (pin "7") (pinfunction "7_7") (pintype "passive"))
    )
    (net (code "67") (name "unconnected-(IOH-Pad9)") (class "Default")
      (node (ref "IOH") (pin "9") (pinfunction "9_9") (pintype "passive"))
    )
    (net (code "68") (name "unconnected-(IOH-Pad10)") (class "Default")
      (node (ref "IOH") (pin "10") (pinfunction "10_10") (pintype "passive"))
    )
    (net (code "69") (name "unconnected-(IOL-Pad3)") (class "Default")
      (node (ref "IOL") (pin "3") (pinfunction "3_3") (pintype "passive"))
    )
    (net (code "70") (name "unconnected-(IOL-Pad4)") (class "Default")
      (node (ref "IOL") (pin "4") (pinfunction "4_4") (pintype "passive"))
    )
    (net (code "71") (name "unconnected-(IOL-Pad5)") (class "Default")
      (node (ref "IOL") (pin "5") (pinfunction "5_5") (pintype "passive"))
    )
    (net (code "72") (name "unconnected-(IOL-Pad7)") (class "Default")
      (node (ref "IOL") (pin "7") (pinfunction "7_7") (pintype "passive"))
    )
    (net (code "73") (name "unconnected-(JP3-Pad1)") (class "Default")
      (node (ref "JP3") (pin "1") (pinfunction "1_1") (pintype "passive"))
    )
    (net (code "74") (name "unconnected-(JP4-Pad1)") (class "Default")
      (node (ref "JP4") (pin "1") (pinfunction "1_1") (pintype "passive"))
    )
    (net (code "75") (name "unconnected-(JP4-Pad6)") (class "Default")
      (node (ref "JP4") (pin "6") (pinfunction "6_6") (pintype "passive"))
    )
    (net (code "76") (name "unconnected-(JP19-Pad1)") (class "Default")
      (node (ref "JP19") (pin "1") (pinfunction "1_1") (pintype "passive"))
    )
    (net (code "77") (name "unconnected-(JP22-Pad1)") (class "Default")
      (node (ref "JP22") (pin "1") (pinfunction "1_1") (pintype "passive"))
    )
    (net (code "78") (name "unconnected-(JP26-Pad1)") (class "Default")
      (node (ref "JP26") (pin "1") (pinfunction "1_1") (pintype "passive"))
    )
    (net (code "79") (name "unconnected-(JP30-Pad1)") (class "Default")
      (node (ref "JP30") (pin "1") (pinfunction "1_1") (pintype "passive"))
    )
    (net (code "80") (name "unconnected-(JP31-Pad1)") (class "Default")
      (node (ref "JP31") (pin "1") (pinfunction "1_1") (pintype "passive"))
    )
    (net (code "81") (name "unconnected-(JP33-Pad1)") (class "Default")
      (node (ref "JP33") (pin "1") (pinfunction "1_1") (pintype "passive"))
    )
    (net (code "82") (name "unconnected-(JP34-Pad1)") (class "Default")
      (node (ref "JP34") (pin "1") (pinfunction "1_1") (pintype "passive"))
    )
    (net (code "83") (name "unconnected-(JP37-Pad1)") (class "Default")
      (node (ref "JP37") (pin "1") (pinfunction "1_1") (pintype "passive"))
    )
    (net (code "84") (name "unconnected-(JP38-Pad1)") (class "Default")
      (node (ref "JP38") (pin "1") (pinfunction "1_1") (pintype "passive"))
    )
    (net (code "85") (name "unconnected-(POWER-Pad1)") (class "Default")
      (node (ref "POWER") (pin "1") (pinfunction "1_1") (pintype "passive"))
    )
    (net (code "86") (name "unconnected-(POWER-Pad2)") (class "Default")
      (node (ref "POWER") (pin "2") (pinfunction "2_2") (pintype "passive"))
    )
    (net (code "87") (name "unconnected-(POWER-Pad3)") (class "Default")
      (node (ref "POWER") (pin "3") (pinfunction "3_3") (pintype "passive"))
    )
    (net (code "88") (name "unconnected-(S1-O-Pad3)") (class "Default")
      (node (ref "S1") (pin "3") (pinfunction "O_3") (pintype "passive"))
    )
    (net (code "89") (name "unconnected-(U$1-PadEX-)") (class "Default")
      (node (ref "U$1") (pin "EX-") (pinfunction "EX-_EX-") (pintype "output"))
    )
    (net (code "90") (name "unconnected-(U$4-*3-Pad6)") (class "Default")
      (node (ref "U$4") (pin "6") (pinfunction "*3_6") (pintype "bidirectional"))
    )
    (net (code "91") (name "unconnected-(U$4-*6-Pad9)") (class "Default")
      (node (ref "U$4") (pin "9") (pinfunction "*6_9") (pintype "bidirectional"))
    )
    (net (code "92") (name "unconnected-(U$4-2-Pad5)") (class "Default")
      (node (ref "U$4") (pin "5") (pinfunction "2_5") (pintype "bidirectional"))
    )
    (net (code "93") (name "unconnected-(U$4-4-Pad7)") (class "Default")
      (node (ref "U$4") (pin "7") (pinfunction "4_7") (pintype "bidirectional"))
    )
    (net (code "94") (name "unconnected-(U$4-GND-Pad23)") (class "Default")
      (node (ref "U$4") (pin "23") (pinfunction "GND_23") (pintype "bidirectional"))
    )
    (net (code "95") (name "unconnected-(U$4-PadA4)") (class "Default")
      (node (ref "U$4") (pin "A4") (pinfunction "A4_A4") (pintype "bidirectional"))
    )
    (net (code "96") (name "unconnected-(U$4-PadA5)") (class "Default")
      (node (ref "U$4") (pin "A5") (pinfunction "A5_A5") (pintype "bidirectional"))
    )
    (net (code "97") (name "unconnected-(U$4-RAW-Pad24)") (class "Default")
      (node (ref "U$4") (pin "24") (pinfunction "RAW_24") (pintype "bidirectional"))
    )
    (net (code "98") (name "unconnected-(U$4-RST-Pad22)") (class "Default")
      (node (ref "U$4") (pin "22") (pinfunction "RST_22") (pintype "bidirectional"))
    )
    (net (code "99") (name "unconnected-(U$5-Pad5)") (class "Default")
      (node (ref "U$5") (pin "5") (pinfunction "5_5") (pintype "passive"))
    )
    (net (code "100") (name "unconnected-(U$5-Pad6)") (class "Default")
      (node (ref "U$5") (pin "6") (pinfunction "6_6") (pintype "passive"))
    )
    (net (code "101") (name "unconnected-(U$5-Pad7)") (class "Default")
      (node (ref "U$5") (pin "7") (pinfunction "7_7") (pintype "passive"))
    )
    (net (code "102") (name "unconnected-(U$5-Pad8)") (class "Default")
      (node (ref "U$5") (pin "8") (pinfunction "8_8") (pintype "passive"))
    )
    (net (code "103") (name "unconnected-(U$5-Pad9)") (class "Default")
      (node (ref "U$5") (pin "9") (pinfunction "9_9") (pintype "passive"))
    )
    (net (code "104") (name "unconnected-(U$5-Pad11)") (class "Default")
      (node (ref "U$5") (pin "11") (pinfunction "11_11") (pintype "passive"))
    )
    (net (code "105") (name "unconnected-(U$5-Pad21)") (class "Default")
      (node (ref "U$5") (pin "21") (pinfunction "21_21") (pintype "passive"))
    )
    (net (code "106") (name "unconnected-(X1-PadD+)") (class "Default")
      (node (ref "X1") (pin "D+") (pinfunction "D+_D+") (pintype "bidirectional"))
    )
    (net (code "107") (name "unconnected-(X1-PadD-)") (class "Default")
      (node (ref "X1") (pin "D-") (pinfunction "D-_D-") (pintype "bidirectional"))
    )
    (net (code "108") (name "unconnected-(X1-PadID)") (class "Default")
      (node (ref "X1") (pin "ID") (pinfunction "ID_ID") (pintype "bidirectional"))
    )
  )
)
